# USB.net
KiCad netlist of a schematic drawn in Altium Designer
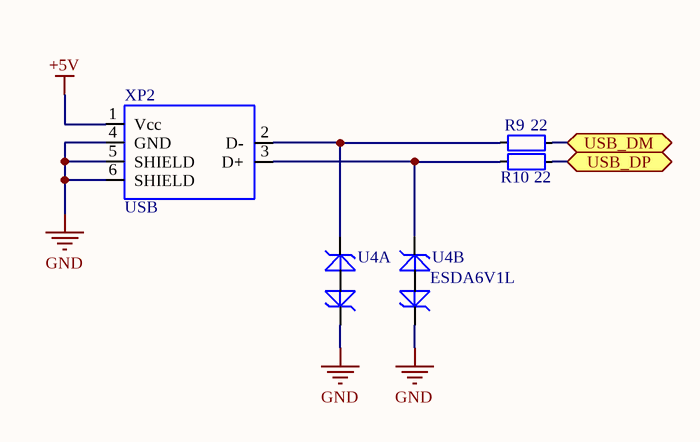
[diagram p0: USB.SchDoc]

(export (version "E")
  (design (tool "Eeschema 10.0.6"))
  (components
    (comp (ref "R9")
      (value "22")
      (footprint "DISCRETE:SMD_0805")
      (description "Resistor")
      (libsource (lib "DISCRETE") (part "RES"))
    )
    (comp (ref "R10")
      (value "22")
      (footprint "DISCRETE:SMD_0805")
      (description "Resistor")
      (libsource (lib "DISCRETE") (part "RES"))
    )
    (comp (ref "U4")
      (value "ESDA6V1L")
      (footprint "ICs:SOT23-3")
      (libsource (lib "ICs") (part "CDSOT23-SM712"))
    )
    (comp (ref "XP2")
      (value "USB")
      (footprint "Connectors:USB/SM2.5-4H4")
      (libsource (lib "Connectors") (part "USB"))
    )
  )
  (nets
    (net (code "1") (name "+5V") (class "Default")
      (node (ref "XP2") (pin "1") (pinfunction "Vcc_1") (pintype "passive"))
    )
    (net (code "2") (name "/USB_DM") (class "Default") (node (ref "R9") (pin "1") (pintype "passive")))
    (net (code "3") (name "/USB_DP") (class "Default") (node (ref "R10") (pin "1") (pintype "passive")))
    (net (code "4") (name "GND") (class "Default")
      (node (ref "U4") (pin "3") (pinfunction "3_3") (pintype "passive"))
      (node (ref "XP2") (pin "4") (pinfunction "GND_4") (pintype "passive"))
      (node (ref "XP2") (pin "5") (pinfunction "SHIELD_5") (pintype "passive"))
      (node (ref "XP2") (pin "6") (pinfunction "SHIELD_6") (pintype "passive"))
    )
    (net (code "5") (name "Net-(XP2-D+)") (class "Default")
      (node (ref "R10") (pin "2") (pintype "passive"))
      (node (ref "U4") (pin "2") (pinfunction "2_2") (pintype "passive"))
      (node (ref "XP2") (pin "3") (pinfunction "D+_3") (pintype "passive"))
    )
    (net (code "6") (name "Net-(XP2-D-)") (class "Default")
      (node (ref "R9") (pin "2") (pintype "passive"))
      (node (ref "U4") (pin "1") (pinfunction "1_1") (pintype "passive"))
      (node (ref "XP2") (pin "2") (pinfunction "D-_2") (pintype "passive"))
    )
  )
)
